# BoardA.net
KiCad netlist of a schematic drawn in Altium Designer
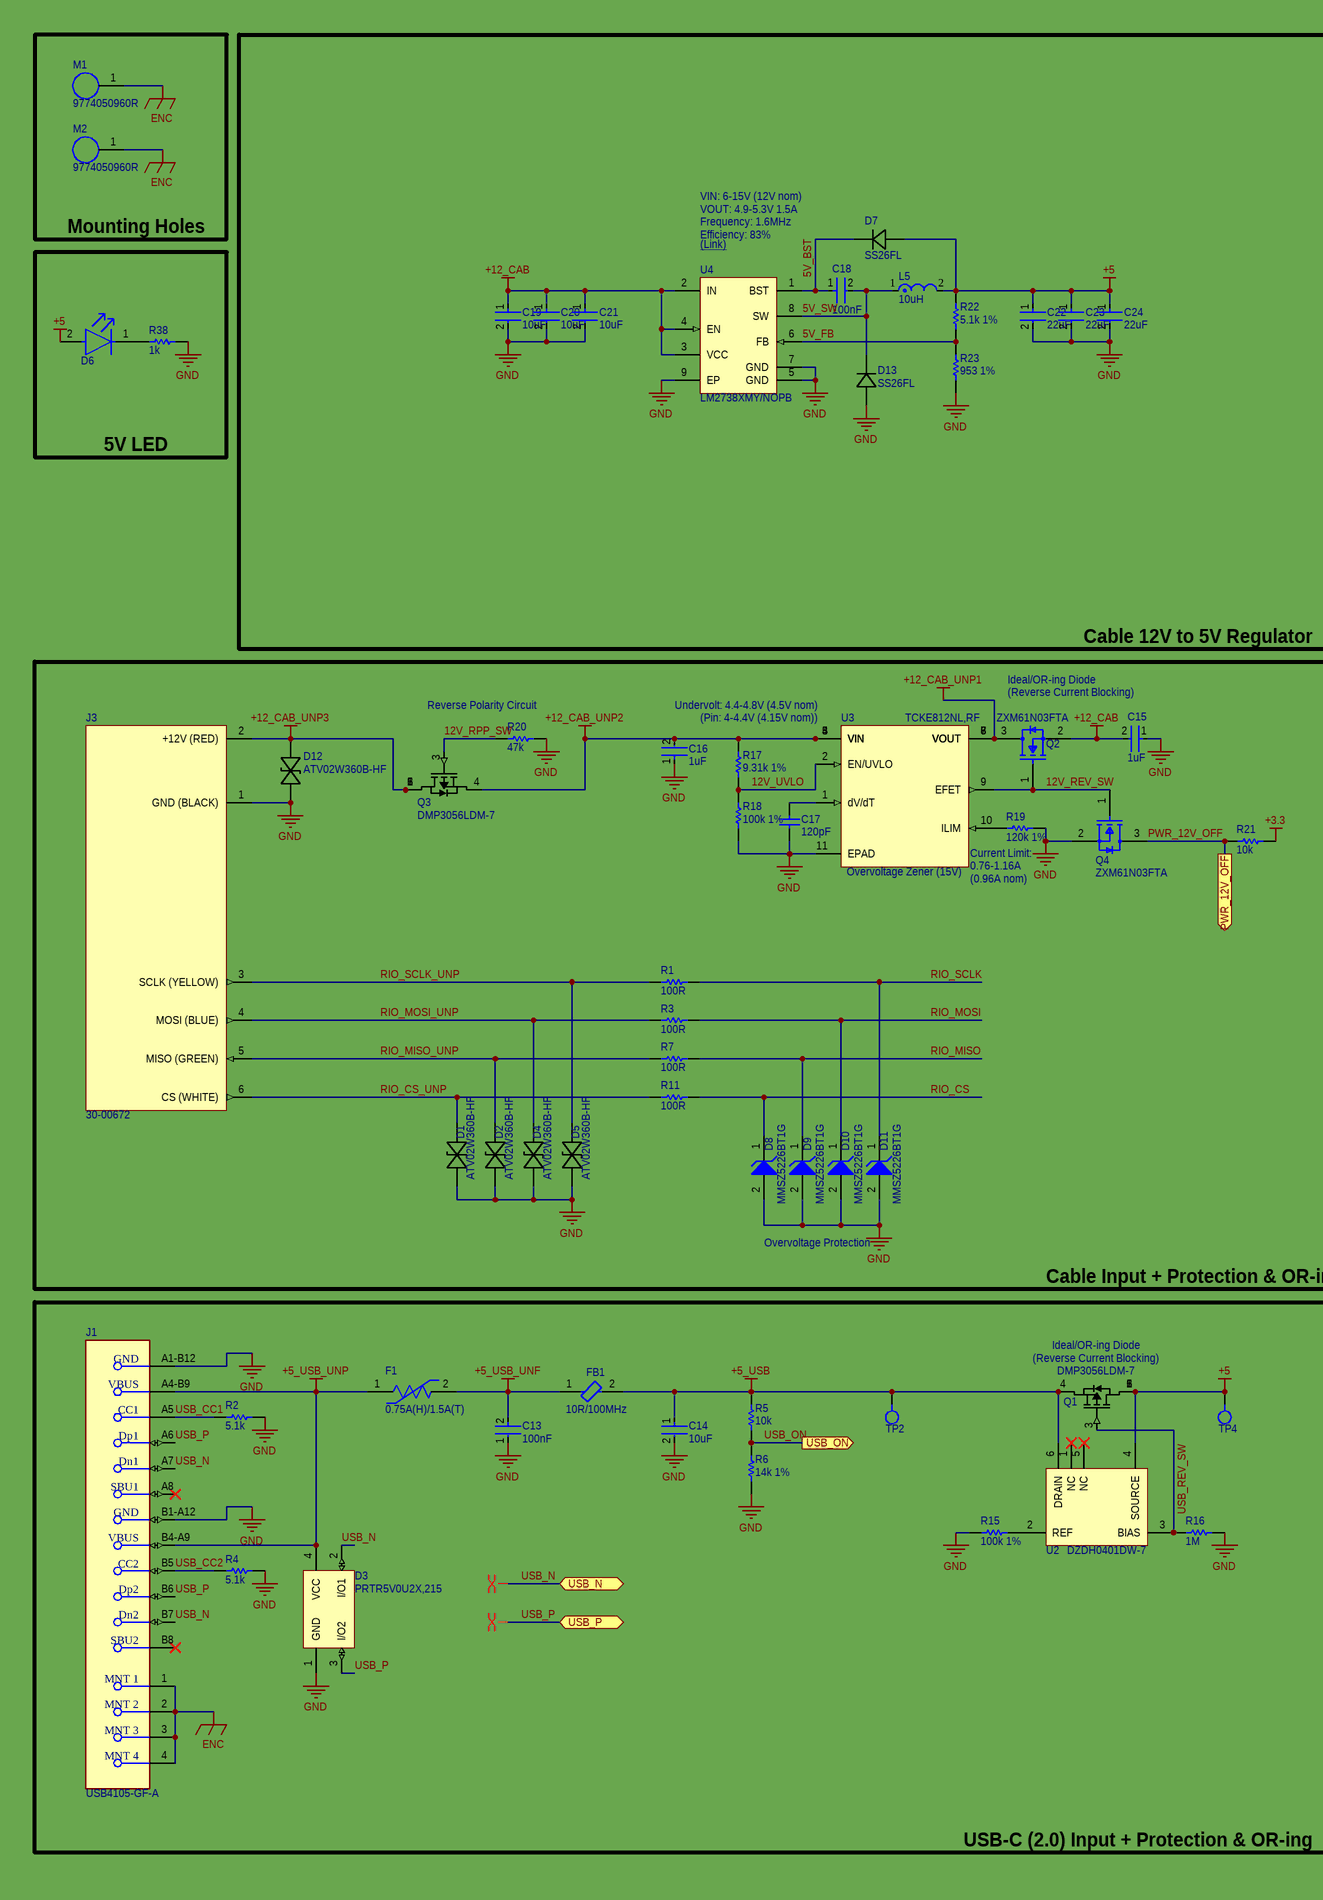
[diagram p0: BoardA.SchDoc, left]
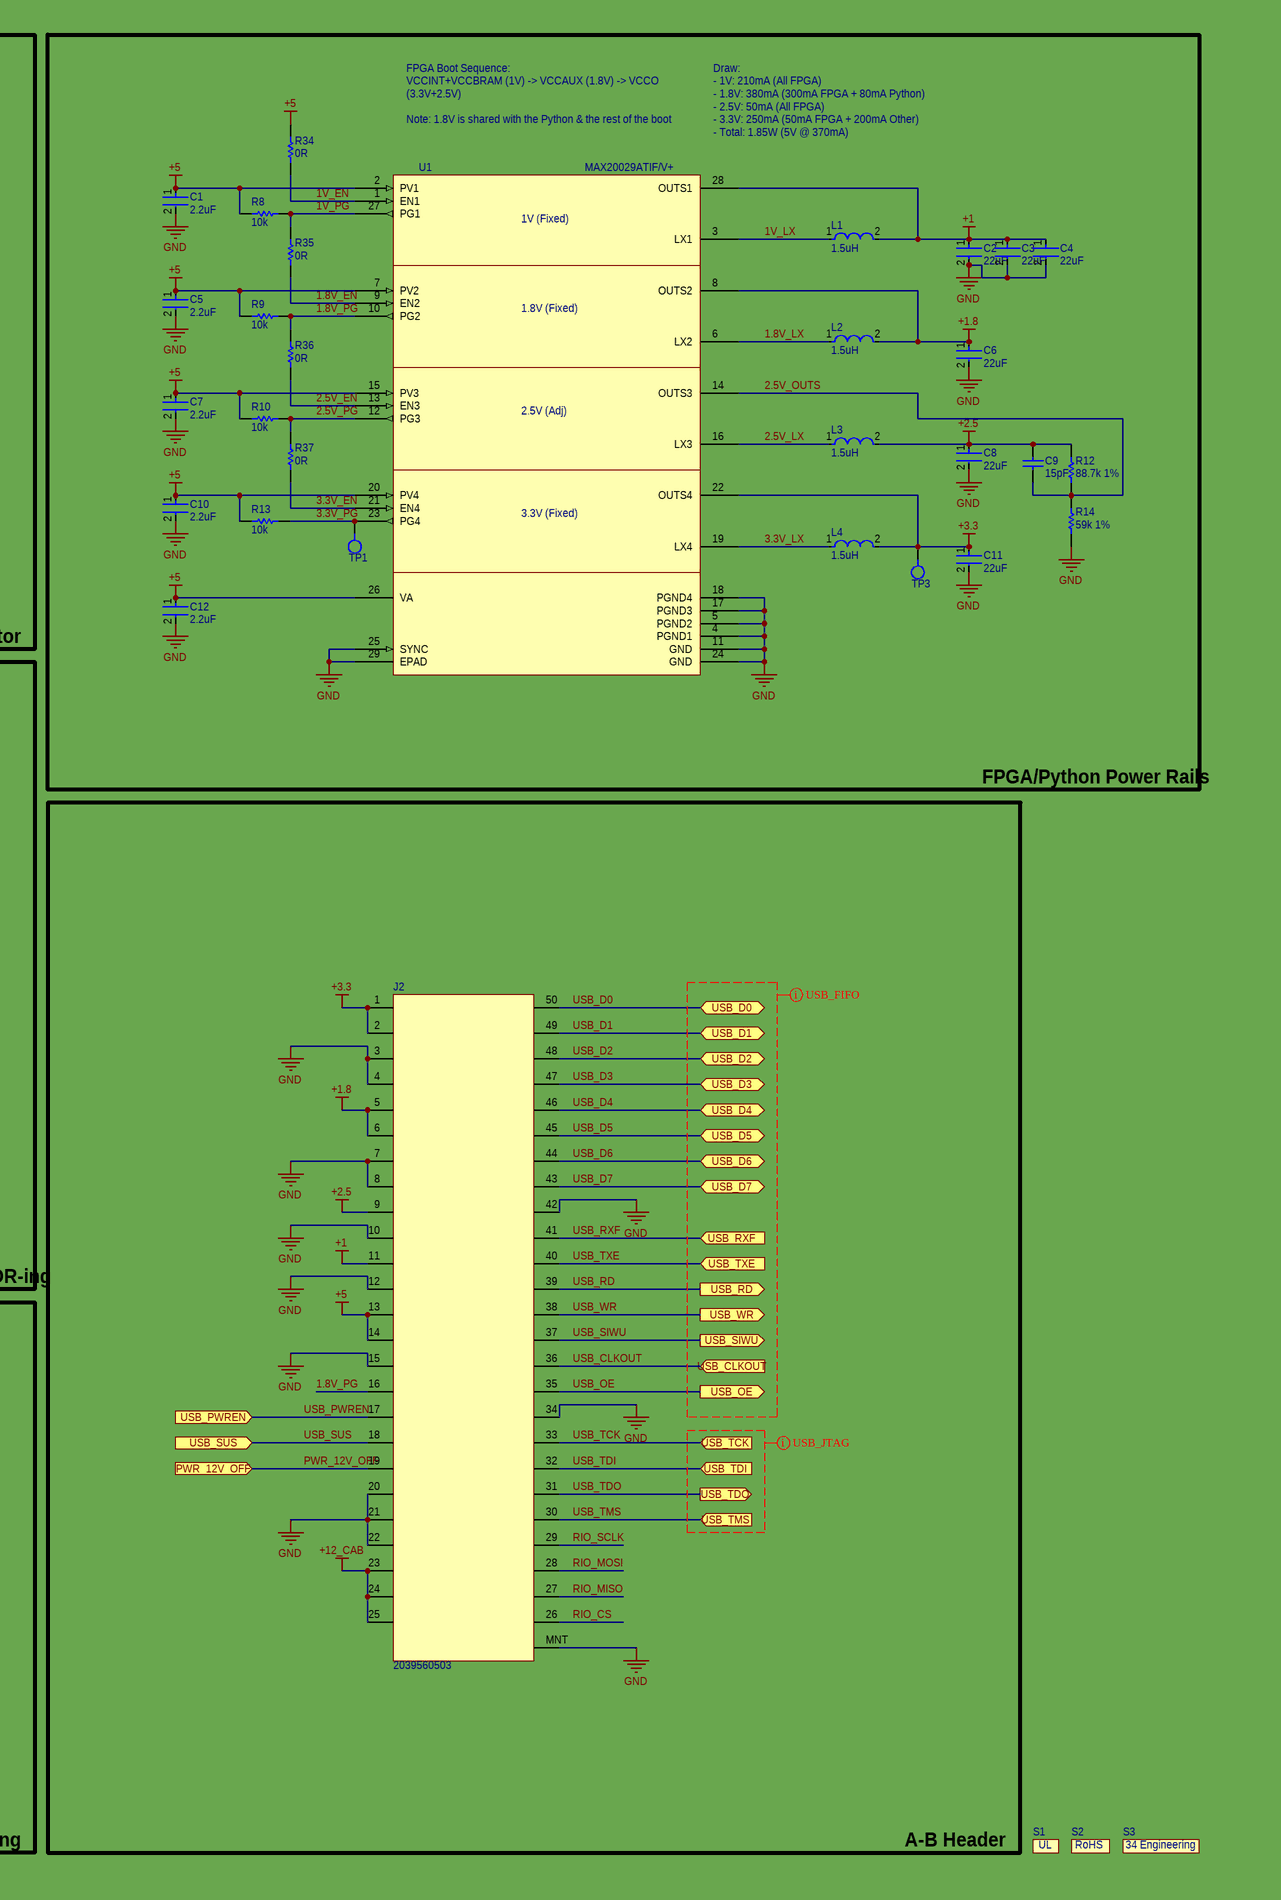
[diagram p1: BoardA.SchDoc, right]

(export (version "E")
  (design (tool "Eeschema 10.0.6"))
  (components
    (comp (ref "C1")
      (value "2.2uF")
      (footprint "FP-C1005-050-0_15-0_1-MFG")
      (description "CAP CER 2.2UF 10V X7S 0402")
      (fields (field (name "TOLERANCE") "10%"))
      (libsource (lib "Altium Content Vault") (part "b4654b650e69147ec39a6b967a45e02"))
    )
    (comp (ref "C2")
      (value "22uF")
      (footprint "FP-GRM21B-0_15-MFG")
      (description "Chip Multilayer Ceramic Capacitors for General Purpose, 0805, 22uF, X5R, 15%, 20%, 6.3V")
      (fields (field (name "VOLTAGE") "6.3V") (field (name "TOLERANCE") "20%"))
      (libsource (lib "Altium Content Vault") (part "b4654b650e69147ec39a6b967a45e02"))
    )
    (comp (ref "C3")
      (value "22uF")
      (footprint "FP-GRM21B-0_15-MFG")
      (description "Chip Multilayer Ceramic Capacitors for General Purpose, 0805, 22uF, X5R, 15%, 20%, 6.3V")
      (fields (field (name "VOLTAGE") "6.3V") (field (name "TOLERANCE") "20%"))
      (libsource (lib "Altium Content Vault") (part "b4654b650e69147ec39a6b967a45e02"))
    )
    (comp (ref "C4")
      (value "22uF")
      (footprint "FP-GRM21B-0_15-MFG")
      (description "Chip Multilayer Ceramic Capacitors for General Purpose, 0805, 22uF, X5R, 15%, 20%, 6.3V")
      (fields (field (name "VOLTAGE") "6.3V") (field (name "TOLERANCE") "20%"))
      (libsource (lib "Altium Content Vault") (part "b4654b650e69147ec39a6b967a45e02"))
    )
    (comp (ref "C5")
      (value "2.2uF")
      (footprint "FP-C1005-050-0_15-0_1-MFG")
      (description "CAP CER 2.2UF 10V X7S 0402")
      (fields (field (name "TOLERANCE") "10%"))
      (libsource (lib "Altium Content Vault") (part "b4654b650e69147ec39a6b967a45e02"))
    )
    (comp (ref "C6")
      (value "22uF")
      (footprint "FP-GRM21B-0_15-MFG")
      (description "Chip Multilayer Ceramic Capacitors for General Purpose, 0805, 22uF, X5R, 15%, 20%, 6.3V")
      (fields (field (name "VOLTAGE") "6.3V") (field (name "TOLERANCE") "20%"))
      (libsource (lib "Altium Content Vault") (part "b4654b650e69147ec39a6b967a45e02"))
    )
    (comp (ref "C7")
      (value "2.2uF")
      (footprint "FP-C1005-050-0_15-0_1-MFG")
      (description "CAP CER 2.2UF 10V X7S 0402")
      (fields (field (name "TOLERANCE") "10%"))
      (libsource (lib "Altium Content Vault") (part "b4654b650e69147ec39a6b967a45e02"))
    )
    (comp (ref "C8")
      (value "22uF")
      (footprint "FP-GRM21B-0_15-MFG")
      (description "Chip Multilayer Ceramic Capacitors for General Purpose, 0805, 22uF, X5R, 15%, 20%, 6.3V")
      (fields (field (name "VOLTAGE") "6.3V") (field (name "TOLERANCE") "20%"))
      (libsource (lib "Altium Content Vault") (part "b4654b650e69147ec39a6b967a45e02"))
    )
    (comp (ref "C9")
      (value "15pF")
      (footprint "CAPC1005X55X25NL05T10")
      (fields (field (name "PART NUMBER") "GRM1555C1H150JZ01D") (field (name "MANUFACTURER") "Murata"))
      (libsource (lib "Altium Content Vault") (part "CAP"))
    )
    (comp (ref "C10")
      (value "2.2uF")
      (footprint "FP-C1005-050-0_15-0_1-MFG")
      (description "CAP CER 2.2UF 10V X7S 0402")
      (fields (field (name "TOLERANCE") "10%"))
      (libsource (lib "Altium Content Vault") (part "b4654b650e69147ec39a6b967a45e02"))
    )
    (comp (ref "C11")
      (value "22uF")
      (footprint "FP-GRM21B-0_15-MFG")
      (description "Chip Multilayer Ceramic Capacitors for General Purpose, 0805, 22uF, X5R, 15%, 20%, 6.3V")
      (fields (field (name "VOLTAGE") "6.3V") (field (name "TOLERANCE") "20%"))
      (libsource (lib "Altium Content Vault") (part "b4654b650e69147ec39a6b967a45e02"))
    )
    (comp (ref "C12")
      (value "2.2uF")
      (footprint "FP-C1005-050-0_15-0_1-MFG")
      (description "CAP CER 2.2UF 10V X7S 0402")
      (fields (field (name "TOLERANCE") "10%"))
      (libsource (lib "Altium Content Vault") (part "b4654b650e69147ec39a6b967a45e02"))
    )
    (comp (ref "C13")
      (value "100nF")
      (footprint "FP-GRM15-IPC_C")
      (description "CAP CER 0.1UF 16V X7R 0402")
      (fields (field (name "MANUFACTURER PART NUMBER") "GRM155R71C104KA88D") (field (name "TOLERANCE") "10%"))
      (libsource (lib "Altium Content Vault") (part "236180d848d6139a670b325ea6854c9"))
    )
    (comp (ref "C14")
      (value "10uF")
      (footprint "FP-CL05A106MP5NUNC-IPC_B")
      (description "CAP CER 10UF 10V X5R 0402")
      (fields
        (field (name "OCTOPART") "https://octopart.com/cl05a106mp5nunc-samsung-22457395")
        (field (name "TOLERANCE") "20%")
      )
      (libsource (lib "Altium Content Vault") (part "b4654b650e69147ec39a6b967a45e02"))
    )
    (comp (ref "C15")
      (value "1uF")
      (footprint "FP-0603-L_1_6_0_1-W_0_8_0-IPC_B")
      (description "None")
      (fields (field (name "TOLERANCE") "10%"))
      (libsource (lib "Altium Content Vault") (part "02cd4be3c70576c341d710602a673aa"))
    )
    (comp (ref "C16")
      (value "1uF")
      (footprint "FP-0603-L_1_6_0_1-W_0_8_0-IPC_B")
      (description "None")
      (fields (field (name "TOLERANCE") "10%"))
      (libsource (lib "Altium Content Vault") (part "02cd4be3c70576c341d710602a673aa"))
    )
    (comp (ref "C17")
      (value "120pF")
      (footprint "CAPC1005X55X25ML05T10")
      (fields (field (name "MANUFACTURER") "Murata") (field (name "PART NUMBER") "GRM1555C1H121JA01D"))
      (libsource (lib "Altium Content Vault") (part "CAP"))
    )
    (comp (ref "C18")
      (value "100nF")
      (footprint "FP-CGA3E-0_3-0_1-IPC_C")
      (description "Cap Ceramic 100nF 50V X7R 10% Pad SMD 0603 +125°C Automotive T/R")
      (fields (field (name "TOLERANCE") "10%") (field (name "VOLTAGE") "50V"))
      (libsource (lib "Altium Content Vault") (part "b4654b650e69147ec39a6b967a45e02"))
    )
    (comp (ref "C19")
      (value "10uF")
      (footprint "FP-GRM188-0_2-MFG")
      (description "Chip Multilayer Ceramic Capacitors for General Purpose, 0603, 10uF, X5R, 15%, 20%, 25V")
      (fields (field (name "TOLERANCE") "20%") (field (name "VOLTAGE") "25V"))
      (libsource (lib "Altium Content Vault") (part "11868f565c42a9108669ba33697ecf6"))
    )
    (comp (ref "C20")
      (value "10uF")
      (footprint "FP-GRM188-0_2-MFG")
      (description "Chip Multilayer Ceramic Capacitors for General Purpose, 0603, 10uF, X5R, 15%, 20%, 25V")
      (fields (field (name "TOLERANCE") "20%") (field (name "VOLTAGE") "25V"))
      (libsource (lib "Altium Content Vault") (part "11868f565c42a9108669ba33697ecf6"))
    )
    (comp (ref "C21")
      (value "10uF")
      (footprint "FP-GRM188-0_2-MFG")
      (description "Chip Multilayer Ceramic Capacitors for General Purpose, 0603, 10uF, X5R, 15%, 20%, 25V")
      (fields (field (name "TOLERANCE") "20%") (field (name "VOLTAGE") "25V"))
      (libsource (lib "Altium Content Vault") (part "11868f565c42a9108669ba33697ecf6"))
    )
    (comp (ref "C22")
      (value "22uF")
      (footprint "FP-GRM21B-0_15-MFG")
      (description "Chip Multilayer Ceramic Capacitors for General Purpose, 0805, 22uF, X5R, 15%, 20%, 6.3V")
      (fields (field (name "VOLTAGE") "6.3V") (field (name "TOLERANCE") "20%"))
      (libsource (lib "Altium Content Vault") (part "b4654b650e69147ec39a6b967a45e02"))
    )
    (comp (ref "C23")
      (value "22uF")
      (footprint "FP-GRM21B-0_15-MFG")
      (description "Chip Multilayer Ceramic Capacitors for General Purpose, 0805, 22uF, X5R, 15%, 20%, 6.3V")
      (fields (field (name "VOLTAGE") "6.3V") (field (name "TOLERANCE") "20%"))
      (libsource (lib "Altium Content Vault") (part "b4654b650e69147ec39a6b967a45e02"))
    )
    (comp (ref "C24")
      (value "22uF")
      (footprint "FP-GRM21B-0_15-MFG")
      (description "Chip Multilayer Ceramic Capacitors for General Purpose, 0805, 22uF, X5R, 15%, 20%, 6.3V")
      (fields (field (name "VOLTAGE") "6.3V") (field (name "TOLERANCE") "20%"))
      (libsource (lib "Altium Content Vault") (part "b4654b650e69147ec39a6b967a45e02"))
    )
    (comp (ref "D1")
      (value "ATV02W360B-HF")
      (footprint "ATV02W")
      (description "No Description Available")
      (fields (field (name "COPYRIGHT") "Copyright (C) 2022 Ultra Librarian. All rights reserved."))
      (libsource (lib "Virtex") (part "ATV02W360B-HF"))
    )
    (comp (ref "D2")
      (value "ATV02W360B-HF")
      (footprint "ATV02W")
      (description "No Description Available")
      (fields (field (name "COPYRIGHT") "Copyright (C) 2022 Ultra Librarian. All rights reserved."))
      (libsource (lib "Virtex") (part "ATV02W360B-HF"))
    )
    (comp (ref "D3")
      (value "PRTR5V0U2X,215")
      (footprint "NXP-SOT143B-4_V")
      (fields (field (name "MANUFACTURER") "NXP Semiconductors"))
      (libsource (lib "Altium Content Vault") (part "NXP-PRTR5V0U2X,215-4"))
    )
    (comp (ref "D4")
      (value "ATV02W360B-HF")
      (footprint "ATV02W")
      (description "No Description Available")
      (fields (field (name "COPYRIGHT") "Copyright (C) 2022 Ultra Librarian. All rights reserved."))
      (libsource (lib "Virtex") (part "ATV02W360B-HF"))
    )
    (comp (ref "D5")
      (value "ATV02W360B-HF")
      (footprint "ATV02W")
      (description "No Description Available")
      (fields (field (name "COPYRIGHT") "Copyright (C) 2022 Ultra Librarian. All rights reserved."))
      (libsource (lib "Virtex") (part "ATV02W360B-HF"))
    )
    (comp (ref "D6")
      (value "SML-D12U1WT86")
      (footprint "FP-SML-D12-MFG")
      (description "LED RED DIFFUSED 1608 SMD")
      (fields
        (field (name "MANUFACTURER") "Rohm")
        (field (name "OCTOPART") "https://octopart.com/sml-d12u1wt86-rohm-70850259")
      )
      (libsource (lib "Altium Content Vault") (part "8706943c75ba83719d021d2fdc84c58"))
    )
    (comp (ref "D7")
      (value "SS26FL")
      (footprint "SS26FL")
      (description "Diode Schottky Barrier Rectifier 60V 2A 2-Pin SOD-123F T/R")
      (fields (field (name "MANUFACTURER") "ON Semiconductor / Fairchild"))
      (libsource (lib "Virtex") (part "SS26FL"))
    )
    (comp (ref "D8")
      (value "MMSZ5226BT1G")
      (footprint "ONSC-SOD-123-2-425-04_V")
      (description "Zener Voltage Regulator, 500 mW, 2-Pin SOD-123, Pb-Free, Tape and Reel")
      (fields (field (name "MANUFACTURER") "On Semiconductor"))
      (libsource (lib "Altium Content Vault") (part "ONSC-K1A2-2"))
    )
    (comp (ref "D9")
      (value "MMSZ5226BT1G")
      (footprint "ONSC-SOD-123-2-425-04_V")
      (description "Zener Voltage Regulator, 500 mW, 2-Pin SOD-123, Pb-Free, Tape and Reel")
      (fields (field (name "MANUFACTURER") "On Semiconductor"))
      (libsource (lib "Altium Content Vault") (part "ONSC-K1A2-2"))
    )
    (comp (ref "D10")
      (value "MMSZ5226BT1G")
      (footprint "ONSC-SOD-123-2-425-04_V")
      (description "Zener Voltage Regulator, 500 mW, 2-Pin SOD-123, Pb-Free, Tape and Reel")
      (fields (field (name "MANUFACTURER") "On Semiconductor"))
      (libsource (lib "Altium Content Vault") (part "ONSC-K1A2-2"))
    )
    (comp (ref "D11")
      (value "MMSZ5226BT1G")
      (footprint "ONSC-SOD-123-2-425-04_V")
      (description "Zener Voltage Regulator, 500 mW, 2-Pin SOD-123, Pb-Free, Tape and Reel")
      (fields (field (name "MANUFACTURER") "On Semiconductor"))
      (libsource (lib "Altium Content Vault") (part "ONSC-K1A2-2"))
    )
    (comp (ref "D12")
      (value "ATV02W360B-HF")
      (footprint "ATV02W")
      (description "No Description Available")
      (fields (field (name "COPYRIGHT") "Copyright (C) 2022 Ultra Librarian. All rights reserved."))
      (libsource (lib "Virtex") (part "ATV02W360B-HF"))
    )
    (comp (ref "D13")
      (value "SS26FL")
      (footprint "SS26FL")
      (description "Diode Schottky Barrier Rectifier 60V 2A 2-Pin SOD-123F T/R")
      (fields (field (name "MANUFACTURER") "ON Semiconductor / Fairchild"))
      (libsource (lib "Virtex") (part "SS26FL"))
    )
    (comp (ref "F1")
      (value "0.75A(H)/1.5A(T)")
      (footprint "FP-0ZCK0075FF2E-MFG")
      (description "PTC RESET FUSE 6V 750MA 0805")
      (libsource (lib "Altium Content Vault") (part "fdf083d5f6389a9a1c4e51137f46658"))
    )
    (comp (ref "FB1")
      (value "10R/100MHz")
      (footprint "FP-BLM15-0_05-IPC_A")
      (description "Chip Ferrite Bead, 0402, 10Ω @ 100MHz, 0.025Ω, 25%, 1A")
      (fields (field (name "TOLERANCE") "25%"))
      (libsource (lib "Altium Content Vault") (part "5f30dd21d616792df468990f7003faa"))
    )
    (comp (ref "J1")
      (value "USB4105-GF-A")
      (footprint "FP-USB4105-GF-A-MFG")
      (description "CONN RCPT USB2.0 TYPEC 5A")
      (fields
        (field (name "MANUFACTURER") "GCT")
        (field (name "OCTOPART") "https://octopart.com/usb4105-gf-a-gct-106627878")
      )
      (libsource (lib "Altium Content Vault") (part "e7c17a616881a82b79941196b4bec10"))
    )
    (comp (ref "J2")
      (value "2039560503")
      (footprint "2039560503")
      (fields (field (name "MANUFACTURER") "Molex") (field (name "MANUFACTURER PART NUMBER") "203956-0503"))
      (libsource (lib "Virtex") (part "2039560503"))
    )
    (comp (ref "J3")
      (value "30-00672")
      (footprint "30-00672")
      (description "Multi-Conductor Cable Braid Thermoplastic Elastomer 6Conductors 28AWG 4.9mm 300V Black")
      (fields (field (name "MANUFACTURER") "Tensility") (field (name "VOLTAGE") "300V"))
      (libsource (lib "Virtex") (part "30-00672"))
    )
    (comp (ref "L1")
      (value "1.5uH")
      (footprint "FP-DFE252012C-IPC_C")
      (description "Shielded Wirewound Inductor 1.5uH 20% 2600mA 0.06Ω 1008 (2520)")
      (fields (field (name "TOLERANCE") "20%"))
      (libsource (lib "Altium Content Vault") (part "725321dda6339637d4d059423bc1c3c"))
    )
    (comp (ref "L2")
      (value "1.5uH")
      (footprint "FP-DFE252012C-IPC_C")
      (description "Shielded Wirewound Inductor 1.5uH 20% 2600mA 0.06Ω 1008 (2520)")
      (fields (field (name "TOLERANCE") "20%"))
      (libsource (lib "Altium Content Vault") (part "725321dda6339637d4d059423bc1c3c"))
    )
    (comp (ref "L3")
      (value "1.5uH")
      (footprint "FP-DFE252012C-IPC_C")
      (description "Shielded Wirewound Inductor 1.5uH 20% 2600mA 0.06Ω 1008 (2520)")
      (fields (field (name "TOLERANCE") "20%"))
      (libsource (lib "Altium Content Vault") (part "725321dda6339637d4d059423bc1c3c"))
    )
    (comp (ref "L4")
      (value "1.5uH")
      (footprint "FP-DFE252012C-IPC_C")
      (description "Shielded Wirewound Inductor 1.5uH 20% 2600mA 0.06Ω 1008 (2520)")
      (fields (field (name "TOLERANCE") "20%"))
      (libsource (lib "Altium Content Vault") (part "725321dda6339637d4d059423bc1c3c"))
    )
    (comp (ref "L5")
      (value "10uH")
      (footprint "FP-VLS6045EX-100M-MFG")
      (description "FIXED IND 10UH 3.4A 61 MOHM SMD")
      (fields (field (name "TOLERANCE") "20%"))
      (libsource (lib "Altium Content Vault") (part "4cc4b267dca4c8e51f7102f422741d8"))
    )
    (comp (ref "M1")
      (value "9774050960R")
      (footprint "9774050960R")
      (description "Spacer Material: Steel Mounting: SMT Series: WA-SMST For ø: 3.3 mm")
      (fields
        (field (name "MANUFACTURER") "Wurth Electronics")
        (field (name "MANUFACTURER PART NUMBER") "9774070960R")
      )
      (libsource (lib "Virtex") (part "9774050960R"))
    )
    (comp (ref "M2")
      (value "9774050960R")
      (footprint "9774050960R")
      (description "Spacer Material: Steel Mounting: SMT Series: WA-SMST For ø: 3.3 mm")
      (fields
        (field (name "MANUFACTURER") "Wurth Electronics")
        (field (name "MANUFACTURER PART NUMBER") "9774070960R")
      )
      (libsource (lib "Virtex") (part "9774050960R"))
    )
    (comp (ref "Q1")
      (value "DMP3056LDM-7")
      (footprint "SOT95P285X130-6N")
      (description "Trans Mosfet P-ch 30V 4.3A 6-PIN SOT-26 T/r / Mosfet P-ch 30V 4.3A SOT-26")
      (fields
        (field (name "MANUFACTURER_PART_NUMBER") "DMG4407SSS-13")
        (field (name "MANUFACTURER") "Diodes")
        (field (name "COPYRIGHT") "Copyright (C) 2022 Ultra Librarian. All rights reserved.")
      )
      (libsource (lib "Virtex") (part "DMP3056LDM-7"))
    )
    (comp (ref "Q2")
      (value "ZXM61N03FTA")
      (footprint "FP-SOT23-MFG")
      (description "MOSFET N-CH 30V 1.4A SOT23-3")
      (fields
        (field (name "MANUFACTURER") "Diodes Inc.")
        (field (name "OCTOPART") "https://octopart.com/zxm61n03fta-diodes+inc.-660007")
      )
      (libsource (lib "Altium Content Vault") (part "f26a002bc83f1905f63347c14e5b235"))
    )
    (comp (ref "Q3")
      (value "DMP3056LDM-7")
      (footprint "SOT95P285X130-6N")
      (description "Trans Mosfet P-ch 30V 4.3A 6-PIN SOT-26 T/r / Mosfet P-ch 30V 4.3A SOT-26")
      (fields
        (field (name "MANUFACTURER_PART_NUMBER") "DMG4407SSS-13")
        (field (name "MANUFACTURER") "Diodes")
        (field (name "COPYRIGHT") "Copyright (C) 2022 Ultra Librarian. All rights reserved.")
      )
      (libsource (lib "Virtex") (part "DMP3056LDM-7"))
    )
    (comp (ref "Q4")
      (value "ZXM61N03FTA")
      (footprint "FP-SOT23-MFG")
      (description "MOSFET N-CH 30V 1.4A SOT23-3")
      (fields
        (field (name "MANUFACTURER") "Diodes Inc.")
        (field (name "OCTOPART") "https://octopart.com/zxm61n03fta-diodes+inc.-660007")
      )
      (libsource (lib "Altium Content Vault") (part "f26a002bc83f1905f63347c14e5b235"))
    )
    (comp (ref "R1")
      (value "100R")
      (footprint "RESC2013X60X35ML10T20")
      (description "Chip Resistor, 100 Ohm, +/-1%, 0.125 W, -55 to 155 degC, 0805 (2012 Metric), RoHS, Tape and Reel")
      (fields (field (name "TOLERANCE") "1%") (field (name "MANUFACTURER") "Yageo"))
      (libsource (lib "Altium Content Vault") (part "RES-2"))
    )
    (comp (ref "R2")
      (value "5.1k")
      (footprint "RESC1005X40X25LL10T10")
      (fields
        (field (name "MANUFACTURER") "TE Connectivity / AMP")
        (field (name "PART NUMBER") "CRG0402F5K1")
      )
      (libsource (lib "Altium Content Vault") (part "RES"))
    )
    (comp (ref "R3")
      (value "100R")
      (footprint "RESC2013X60X35ML10T20")
      (description "Chip Resistor, 100 Ohm, +/-1%, 0.125 W, -55 to 155 degC, 0805 (2012 Metric), RoHS, Tape and Reel")
      (fields (field (name "TOLERANCE") "1%") (field (name "MANUFACTURER") "Yageo"))
      (libsource (lib "Altium Content Vault") (part "RES-2"))
    )
    (comp (ref "R4")
      (value "5.1k")
      (footprint "RESC1005X40X25LL10T10")
      (fields
        (field (name "MANUFACTURER") "TE Connectivity / AMP")
        (field (name "PART NUMBER") "CRG0402F5K1")
      )
      (libsource (lib "Altium Content Vault") (part "RES"))
    )
    (comp (ref "R5")
      (value "10k")
      (footprint "RESC1005X40X25LL05T05")
      (description "Chip Resistor, 10 KOhm, +/- 1%, 0.1 W, -55 to 155 degC, 0402 (1005 Metric), RoHS, Tape and Reel")
      (fields (field (name "TOLERANCE") "1%") (field (name "MANUFACTURER") "Panasonic"))
      (libsource (lib "Altium Content Vault") (part "RES-2"))
    )
    (comp (ref "R6")
      (value "14k 1%")
      (footprint "RESC1005X40X25ML05T05")
      (fields (field (name "MANUFACTURER") "Panasonic") (field (name "PART NUMBER") "ERJ-2RKF1402X"))
      (libsource (lib "Altium Content Vault") (part "RES"))
    )
    (comp (ref "R7")
      (value "100R")
      (footprint "RESC2013X60X35ML10T20")
      (description "Chip Resistor, 100 Ohm, +/-1%, 0.125 W, -55 to 155 degC, 0805 (2012 Metric), RoHS, Tape and Reel")
      (fields (field (name "TOLERANCE") "1%") (field (name "MANUFACTURER") "Yageo"))
      (libsource (lib "Altium Content Vault") (part "RES-2"))
    )
    (comp (ref "R8")
      (value "10k")
      (footprint "RESC1005X40X25LL05T05")
      (description "Chip Resistor, 10 KOhm, +/- 1%, 0.1 W, -55 to 155 degC, 0402 (1005 Metric), RoHS, Tape and Reel")
      (fields (field (name "TOLERANCE") "1%") (field (name "MANUFACTURER") "Panasonic"))
      (libsource (lib "Altium Content Vault") (part "RES-2"))
    )
    (comp (ref "R9")
      (value "10k")
      (footprint "RESC1005X40X25LL05T05")
      (description "Chip Resistor, 10 KOhm, +/- 1%, 0.1 W, -55 to 155 degC, 0402 (1005 Metric), RoHS, Tape and Reel")
      (fields (field (name "TOLERANCE") "1%") (field (name "MANUFACTURER") "Panasonic"))
      (libsource (lib "Altium Content Vault") (part "RES-2"))
    )
    (comp (ref "R10")
      (value "10k")
      (footprint "RESC1005X40X25LL05T05")
      (description "Chip Resistor, 10 KOhm, +/- 1%, 0.1 W, -55 to 155 degC, 0402 (1005 Metric), RoHS, Tape and Reel")
      (fields (field (name "TOLERANCE") "1%") (field (name "MANUFACTURER") "Panasonic"))
      (libsource (lib "Altium Content Vault") (part "RES-2"))
    )
    (comp (ref "R11")
      (value "100R")
      (footprint "RESC2013X60X35ML10T20")
      (description "Chip Resistor, 100 Ohm, +/-1%, 0.125 W, -55 to 155 degC, 0805 (2012 Metric), RoHS, Tape and Reel")
      (fields (field (name "TOLERANCE") "1%") (field (name "MANUFACTURER") "Yageo"))
      (libsource (lib "Altium Content Vault") (part "RES-2"))
    )
    (comp (ref "R12")
      (value "88.7k 1%")
      (footprint "RESC1005X40X25NL05T05")
      (fields (field (name "MANUFACTURER") "Vishay Dale") (field (name "PART NUMBER") "CRCW040288K7FKED"))
      (libsource (lib "Altium Content Vault") (part "RES"))
    )
    (comp (ref "R13")
      (value "10k")
      (footprint "RESC1005X40X25LL05T05")
      (description "Chip Resistor, 10 KOhm, +/- 1%, 0.1 W, -55 to 155 degC, 0402 (1005 Metric), RoHS, Tape and Reel")
      (fields (field (name "TOLERANCE") "1%") (field (name "MANUFACTURER") "Panasonic"))
      (libsource (lib "Altium Content Vault") (part "RES-2"))
    )
    (comp (ref "R14")
      (value "59k 1%")
      (footprint "RESC1005X40X25LL05T05")
      (fields (field (name "PART NUMBER") "CRCW040259K0FKED") (field (name "MANUFACTURER") "Vishay Dale"))
      (libsource (lib "Altium Content Vault") (part "RES"))
    )
    (comp (ref "R15")
      (value "100k 1%")
      (footprint "RESC1005X40X25NL05T10")
      (fields (field (name "PART NUMBER") "RC0402FR-07100KL") (field (name "MANUFACTURER") "Yageo / Phycomp"))
      (libsource (lib "Altium Content Vault") (part "RES"))
    )
    (comp (ref "R16")
      (value "1M")
      (footprint "RESC1005X40X25LL05T05")
      (description "Chip Resistor, 1 MOhm, +/- 1%, 100 mW, -55 to 155 degC, 0402 (1005 Metric), RoHS, Tape and Reel")
      (fields (field (name "PARTNUMBER") "ERJ-2RKF1004X") (field (name "TOLERANCE") "1%"))
      (libsource (lib "Altium Content Vault") (part "RES-2"))
    )
    (comp (ref "R17")
      (value "9.31k 1%")
      (footprint "RESC1005X40X25NL05T05")
      (fields (field (name "PART NUMBER") "ERJ-2RKF9311X") (field (name "MANUFACTURER") "Panasonic"))
      (libsource (lib "Altium Content Vault") (part "RES"))
    )
    (comp (ref "R18")
      (value "100k 1%")
      (footprint "RESC1005X40X25NL05T10")
      (fields (field (name "PART NUMBER") "RC0402FR-07100KL") (field (name "MANUFACTURER") "Yageo / Phycomp"))
      (libsource (lib "Altium Content Vault") (part "RES"))
    )
    (comp (ref "R19")
      (value "120k 1%")
      (footprint "RESC1005X40X25NL05T05")
      (fields (field (name "PART NUMBER") "ERJ2RKF1203X") (field (name "MANUFACTURER") "Panasonic"))
      (libsource (lib "Altium Content Vault") (part "RES"))
    )
    (comp (ref "R20")
      (value "47k")
      (footprint "RESC1608X55X30NL15T15")
      (description "Chip Resistor, 47 KOhm, +/- 1%, 0.1 W, -55 to 155 degC, 0603 (1608 Metric), RoHS, Tape and Reel")
      (libsource (lib "Altium Content Vault") (part "RES-2"))
    )
    (comp (ref "R21")
      (value "10k")
      (footprint "RESC1005X40X25LL05T05")
      (description "Chip Resistor, 10 KOhm, +/- 1%, 0.1 W, -55 to 155 degC, 0402 (1005 Metric), RoHS, Tape and Reel")
      (fields (field (name "TOLERANCE") "1%") (field (name "MANUFACTURER") "Panasonic"))
      (libsource (lib "Altium Content Vault") (part "RES-2"))
    )
    (comp (ref "R22")
      (value "5.1k 1%")
      (footprint "RESC1608X55X30NL15T15")
      (fields (field (name "PART NUMBER") "ERJ-3EKF5101V") (field (name "MANUFACTURER") "Panasonic"))
      (libsource (lib "Altium Content Vault") (part "RES"))
    )
    (comp (ref "R23")
      (value "953 1%")
      (footprint "RESC1608X55X30NL15T15")
      (fields (field (name "PART NUMBER") "ERJ-3EKF9530V") (field (name "MANUFACTURER") "Panasonic"))
      (libsource (lib "Altium Content Vault") (part "RES"))
    )
    (comp (ref "R34")
      (value "0R")
      (footprint "RESC1005X40X25NL05T10")
      (fields (field (name "MANUFACTURER") "Yageo / Phycomp") (field (name "PART NUMBER") "RC0402JR-070RL"))
      (libsource (lib "Altium Content Vault") (part "RES"))
    )
    (comp (ref "R35")
      (value "0R")
      (footprint "RESC1005X40X25NL05T10")
      (fields (field (name "MANUFACTURER") "Yageo / Phycomp") (field (name "PART NUMBER") "RC0402JR-070RL"))
      (libsource (lib "Altium Content Vault") (part "RES"))
    )
    (comp (ref "R36")
      (value "0R")
      (footprint "RESC1005X40X25NL05T10")
      (fields (field (name "MANUFACTURER") "Yageo / Phycomp") (field (name "PART NUMBER") "RC0402JR-070RL"))
      (libsource (lib "Altium Content Vault") (part "RES"))
    )
    (comp (ref "R37")
      (value "0R")
      (footprint "RESC1005X40X25NL05T10")
      (fields (field (name "MANUFACTURER") "Yageo / Phycomp") (field (name "PART NUMBER") "RC0402JR-070RL"))
      (libsource (lib "Altium Content Vault") (part "RES"))
    )
    (comp (ref "R38")
      (value "1k")
      (footprint "RESC1005X40X25NL05T05")
      (description "Chip Resistor, 1 KOhm, +/- 1%, 100 mW, -55 to 155 degC, 0402 (1005 Metric), RoHS, Tape and Reel")
      (fields (field (name "PARTNUMBER") "ERJ-2RKF1001X") (field (name "MANUFACTURER") "Basic Passives"))
      (libsource (lib "Altium Content Vault") (part "RES-2"))
    )
    (comp (ref "S1") (value "~") (footprint "UL") (libsource (lib "Virtex") (part "UL")))
    (comp (ref "S2") (value "~") (footprint "RoHS") (libsource (lib "Virtex") (part "RoHS")))
    (comp (ref "S3")
      (value "~")
      (footprint "34EngineeringLogo")
      (description "34 Engineering Silkscreen Logo")
      (libsource (lib "Virtex") (part "34EngineeringLogo"))
    )
    (comp (ref "TP1")
      (value "~")
      (footprint "TestPoint1mm")
      (description "Test Point 1mm Diameter")
      (libsource (lib "Virtex") (part "TestPoint1mm"))
    )
    (comp (ref "TP2")
      (value "~")
      (footprint "TestPoint1mm")
      (description "Test Point 1mm Diameter")
      (libsource (lib "Virtex") (part "TestPoint1mm"))
    )
    (comp (ref "TP3")
      (value "~")
      (footprint "TestPoint1mm")
      (description "Test Point 1mm Diameter")
      (libsource (lib "Virtex") (part "TestPoint1mm"))
    )
    (comp (ref "TP4")
      (value "~")
      (footprint "TestPoint1mm")
      (description "Test Point 1mm Diameter")
      (libsource (lib "Virtex") (part "TestPoint1mm"))
    )
    (comp (ref "U1")
      (value "MAX20029ATIF/V+")
      (footprint "MAX20029ATIF/V+")
      (description "DC to DC Converter Quad Step-Down 3V to 5.5V Automotive 28-Pin TQFN Tube")
      (fields
        (field (name "MANUFACTURER") "Maxim")
        (field (name "COPYRIGHT") "Copyright (C) 2022 Ultra Librarian. All rights reserved.")
      )
      (libsource (lib "Virtex") (part "MAX20029ATIF/V+"))
    )
    (comp (ref "U2")
      (value "DZDH0401DW-7")
      (footprint "DZDH0401DW-7")
      (description "Ideal Diode Controller 40V 300mA 300mW 6-Pin SOT-363 T/R")
      (fields
        (field (name "MANUFACTURER") "Diodes")
        (field (name "COPYRIGHT") "Copyright (C) 2022 Ultra Librarian. All rights reserved.")
      )
      (libsource (lib "Virtex") (part "DZDH0401DW-7"))
    )
    (comp (ref "U3")
      (value "TCKE812NL,RF")
      (footprint "WSON10B_TOS")
      (description "5.1V Voltage Clmp Latch Type")
      (fields (field (name "MANUFACTURER") "Toshiba") (field (name "MANUFACTURER PART NUMBER") "TCKE812NLRF"))
      (libsource (lib "Virtex") (part "TCKE812NL,RF"))
    )
    (comp (ref "U4")
      (value "LM2738XMY/NOPB")
      (footprint "DGN0008A_N")
      (description "550kHz/1.6MHz 1.5A Step-Down DC-DC Switching Regulator, 8-pin eMSOP, Pb-Free")
      (fields (field (name "MANUFACTURER") "Texas Instruments"))
      (libsource (lib "Altium Content Vault") (part "PM-SWREG-LM2738-9"))
    )
  )
  (nets
    (net (code "1") (name "+1") (class "Default")
      (node (ref "C2") (pin "1") (pinfunction "1_1") (pintype "passive"))
      (node (ref "C3") (pin "1") (pinfunction "1_1") (pintype "passive"))
      (node (ref "C4") (pin "1") (pinfunction "1_1") (pintype "passive"))
      (node (ref "J2") (pin "11") (pintype "passive"))
      (node (ref "L1") (pin "2") (pinfunction "2_2") (pintype "passive"))
      (node (ref "U1") (pin "28") (pinfunction "OUTS1_28") (pintype "power_in"))
    )
    (net (code "2") (name "+1.8") (class "Default")
      (node (ref "C6") (pin "1") (pinfunction "1_1") (pintype "passive"))
      (node (ref "J2") (pin "5") (pintype "passive"))
      (node (ref "J2") (pin "6") (pintype "passive"))
      (node (ref "L2") (pin "2") (pinfunction "2_2") (pintype "passive"))
      (node (ref "U1") (pin "8") (pinfunction "OUTS2_8") (pintype "power_in"))
    )
    (net (code "3") (name "+2.5") (class "Default")
      (node (ref "C8") (pin "1") (pinfunction "1_1") (pintype "passive"))
      (node (ref "C9") (pin "2") (pinfunction "2_2") (pintype "passive"))
      (node (ref "J2") (pin "9") (pintype "passive"))
      (node (ref "L3") (pin "2") (pinfunction "2_2") (pintype "passive"))
      (node (ref "R12") (pin "2") (pinfunction "2_2") (pintype "passive"))
    )
    (net (code "4") (name "+3.3") (class "Default")
      (node (ref "C11") (pin "1") (pinfunction "1_1") (pintype "passive"))
      (node (ref "J2") (pin "1") (pintype "passive"))
      (node (ref "J2") (pin "2") (pintype "passive"))
      (node (ref "L4") (pin "2") (pinfunction "2_2") (pintype "passive"))
      (node (ref "R21") (pin "2") (pinfunction "2_2") (pintype "passive"))
      (node (ref "TP3") (pin "1") (pintype "passive"))
      (node (ref "U1") (pin "22") (pinfunction "OUTS4_22") (pintype "power_in"))
    )
    (net (code "5") (name "+5") (class "Default")
      (node (ref "C1") (pin "1") (pinfunction "1_1") (pintype "passive"))
      (node (ref "C10") (pin "1") (pinfunction "1_1") (pintype "passive"))
      (node (ref "C12") (pin "1") (pinfunction "1_1") (pintype "passive"))
      (node (ref "C22") (pin "1") (pinfunction "1_1") (pintype "passive"))
      (node (ref "C23") (pin "1") (pinfunction "1_1") (pintype "passive"))
      (node (ref "C24") (pin "1") (pinfunction "1_1") (pintype "passive"))
      (node (ref "C5") (pin "1") (pinfunction "1_1") (pintype "passive"))
      (node (ref "C7") (pin "1") (pinfunction "1_1") (pintype "passive"))
      (node (ref "D6") (pin "2") (pinfunction "A_2") (pintype "passive"))
      (node (ref "D7") (pin "2") (pinfunction "2_2") (pintype "passive"))
      (node (ref "J2") (pin "13") (pintype "passive"))
      (node (ref "J2") (pin "14") (pintype "passive"))
      (node (ref "L5") (pin "2") (pinfunction "2_2") (pintype "passive"))
      (node (ref "Q1") (pin "1") (pintype "power_in"))
      (node (ref "Q1") (pin "2") (pintype "power_in"))
      (node (ref "Q1") (pin "5") (pintype "power_in"))
      (node (ref "Q1") (pin "6") (pintype "power_in"))
      (node (ref "R10") (pin "1") (pinfunction "1_1") (pintype "passive"))
      (node (ref "R13") (pin "1") (pinfunction "1_1") (pintype "passive"))
      (node (ref "R22") (pin "2") (pinfunction "2_2") (pintype "passive"))
      (node (ref "R34") (pin "2") (pinfunction "2_2") (pintype "passive"))
      (node (ref "R8") (pin "1") (pinfunction "1_1") (pintype "passive"))
      (node (ref "R9") (pin "1") (pinfunction "1_1") (pintype "passive"))
      (node (ref "TP4") (pin "1") (pintype "passive"))
      (node (ref "U1") (pin "15") (pinfunction "PV3_15") (pintype "input"))
      (node (ref "U1") (pin "2") (pinfunction "PV1_2") (pintype "input"))
      (node (ref "U1") (pin "20") (pinfunction "PV4_20") (pintype "input"))
      (node (ref "U1") (pin "26") (pinfunction "VA_26") (pintype "power_in"))
      (node (ref "U1") (pin "7") (pinfunction "PV2_7") (pintype "input"))
      (node (ref "U2") (pin "4") (pinfunction "SOURCE_4") (pintype "passive"))
    )
    (net (code "6") (name "+5_USB") (class "Default")
      (node (ref "C14") (pin "1") (pinfunction "1_1") (pintype "passive"))
      (node (ref "FB1") (pin "2") (pinfunction "2_2") (pintype "passive"))
      (node (ref "Q1") (pin "4") (pintype "power_in"))
      (node (ref "R5") (pin "2") (pinfunction "2_2") (pintype "passive"))
      (node (ref "TP2") (pin "1") (pintype "passive"))
      (node (ref "U2") (pin "6") (pinfunction "DRAIN_6") (pintype "passive"))
    )
    (net (code "7") (name "+5_USB_UNF") (class "Default")
      (node (ref "C13") (pin "2") (pinfunction "2_2") (pintype "passive"))
      (node (ref "F1") (pin "2") (pinfunction "2_2") (pintype "passive"))
      (node (ref "FB1") (pin "1") (pinfunction "1_1") (pintype "passive"))
    )
    (net (code "8") (name "+5_USB_UNP") (class "Default")
      (node (ref "D3") (pin "4") (pinfunction "VCC_4") (pintype "power_in"))
      (node (ref "F1") (pin "1") (pinfunction "1_1") (pintype "passive"))
      (node (ref "J1") (pin "A4-B9") (pinfunction "VBUS_A4-B9") (pintype "power_in"))
      (node (ref "J1") (pin "B4-A9") (pinfunction "VBUS_B4-A9") (pintype "bidirectional"))
    )
    (net (code "9") (name "+12_CAB") (class "Default")
      (node (ref "C15") (pin "2") (pinfunction "2_2") (pintype "passive"))
      (node (ref "C19") (pin "1") (pinfunction "1_1") (pintype "passive"))
      (node (ref "C20") (pin "1") (pinfunction "1_1") (pintype "passive"))
      (node (ref "C21") (pin "1") (pinfunction "1_1") (pintype "passive"))
      (node (ref "J2") (pin "23") (pintype "passive"))
      (node (ref "J2") (pin "24") (pintype "passive"))
      (node (ref "J2") (pin "25") (pintype "passive"))
      (node (ref "Q2") (pin "2") (pinfunction "S_2") (pintype "passive"))
      (node (ref "U4") (pin "2") (pinfunction "IN_2") (pintype "power_in"))
      (node (ref "U4") (pin "3") (pinfunction "VCC_3") (pintype "power_in"))
      (node (ref "U4") (pin "4") (pinfunction "EN_4") (pintype "input"))
    )
    (net (code "10") (name "+12_CAB_UNP1") (class "Default")
      (node (ref "Q2") (pin "3") (pinfunction "D_3") (pintype "passive"))
      (node (ref "U3") (pin "6") (pinfunction "VOUT_6") (pintype "power_in"))
      (node (ref "U3") (pin "7") (pinfunction "VOUT_7") (pintype "power_in"))
      (node (ref "U3") (pin "8") (pinfunction "VOUT_8") (pintype "power_in"))
    )
    (net (code "11") (name "+12_CAB_UNP2") (class "Default")
      (node (ref "C16") (pin "2") (pinfunction "2_2") (pintype "passive"))
      (node (ref "Q3") (pin "4") (pintype "power_in"))
      (node (ref "R17") (pin "2") (pinfunction "2_2") (pintype "passive"))
      (node (ref "U3") (pin "3") (pinfunction "VIN_3") (pintype "power_in"))
      (node (ref "U3") (pin "4") (pinfunction "VIN_4") (pintype "power_in"))
      (node (ref "U3") (pin "5") (pinfunction "VIN_5") (pintype "power_in"))
    )
    (net (code "12") (name "+12_CAB_UNP3") (class "Default")
      (node (ref "D12") (pin "2") (pinfunction "2_2") (pintype "passive"))
      (node (ref "J3") (pin "2") (pinfunction "+12V_(RED)_2") (pintype "power_in"))
      (node (ref "Q3") (pin "1") (pintype "power_in"))
      (node (ref "Q3") (pin "2") (pintype "power_in"))
      (node (ref "Q3") (pin "5") (pintype "power_in"))
      (node (ref "Q3") (pin "6") (pintype "power_in"))
    )
    (net (code "13") (name "/1.8V_EN") (class "Default")
      (node (ref "R35") (pin "1") (pinfunction "1_1") (pintype "passive"))
      (node (ref "U1") (pin "9") (pinfunction "EN2_9") (pintype "input"))
    )
    (net (code "14") (name "/1.8V_LX") (class "Default")
      (node (ref "L2") (pin "1") (pinfunction "1_1") (pintype "passive"))
      (node (ref "U1") (pin "6") (pinfunction "LX2_6") (pintype "power_in"))
    )
    (net (code "15") (name "/1.8V_PG") (class "Default")
      (node (ref "J2") (pin "16") (pintype "passive"))
      (node (ref "R36") (pin "2") (pinfunction "2_2") (pintype "passive"))
      (node (ref "R9") (pin "2") (pinfunction "2_2") (pintype "passive"))
      (node (ref "U1") (pin "10") (pinfunction "PG2_10") (pintype "output"))
    )
    (net (code "16") (name "/1V_EN") (class "Default")
      (node (ref "R34") (pin "1") (pinfunction "1_1") (pintype "passive"))
      (node (ref "U1") (pin "1") (pinfunction "EN1_1") (pintype "input"))
    )
    (net (code "17") (name "/1V_LX") (class "Default")
      (node (ref "L1") (pin "1") (pinfunction "1_1") (pintype "passive"))
      (node (ref "U1") (pin "3") (pinfunction "LX1_3") (pintype "power_in"))
    )
    (net (code "18") (name "/1V_PG") (class "Default")
      (node (ref "R35") (pin "2") (pinfunction "2_2") (pintype "passive"))
      (node (ref "R8") (pin "2") (pinfunction "2_2") (pintype "passive"))
      (node (ref "U1") (pin "27") (pinfunction "PG1_27") (pintype "output"))
    )
    (net (code "19") (name "/2.5V_EN") (class "Default")
      (node (ref "R36") (pin "1") (pinfunction "1_1") (pintype "passive"))
      (node (ref "U1") (pin "13") (pinfunction "EN3_13") (pintype "input"))
    )
    (net (code "20") (name "/2.5V_LX") (class "Default")
      (node (ref "L3") (pin "1") (pinfunction "1_1") (pintype "passive"))
      (node (ref "U1") (pin "16") (pinfunction "LX3_16") (pintype "power_in"))
    )
    (net (code "21") (name "/2.5V_OUTS") (class "Default")
      (node (ref "C9") (pin "1") (pinfunction "1_1") (pintype "passive"))
      (node (ref "R12") (pin "1") (pinfunction "1_1") (pintype "passive"))
      (node (ref "R14") (pin "2") (pinfunction "2_2") (pintype "passive"))
      (node (ref "U1") (pin "14") (pinfunction "OUTS3_14") (pintype "power_in"))
    )
    (net (code "22") (name "/2.5V_PG") (class "Default")
      (node (ref "R10") (pin "2") (pinfunction "2_2") (pintype "passive"))
      (node (ref "R37") (pin "2") (pinfunction "2_2") (pintype "passive"))
      (node (ref "U1") (pin "12") (pinfunction "PG3_12") (pintype "output"))
    )
    (net (code "23") (name "/3.3V_EN") (class "Default")
      (node (ref "R37") (pin "1") (pinfunction "1_1") (pintype "passive"))
      (node (ref "U1") (pin "21") (pinfunction "EN4_21") (pintype "input"))
    )
    (net (code "24") (name "/3.3V_LX") (class "Default")
      (node (ref "L4") (pin "1") (pinfunction "1_1") (pintype "passive"))
      (node (ref "U1") (pin "19") (pinfunction "LX4_19") (pintype "power_in"))
    )
    (net (code "25") (name "/3.3V_PG") (class "Default")
      (node (ref "R13") (pin "2") (pinfunction "2_2") (pintype "passive"))
      (node (ref "TP1") (pin "1") (pintype "passive"))
      (node (ref "U1") (pin "23") (pinfunction "PG4_23") (pintype "output"))
    )
    (net (code "26") (name "/5V_BST") (class "Default")
      (node (ref "C18") (pin "1") (pinfunction "1_1") (pintype "passive"))
      (node (ref "D7") (pin "1") (pinfunction "1_1") (pintype "passive"))
      (node (ref "U4") (pin "1") (pinfunction "BST_1") (pintype "passive"))
    )
    (net (code "27") (name "/5V_FB") (class "Default")
      (node (ref "R22") (pin "1") (pinfunction "1_1") (pintype "passive"))
      (node (ref "R23") (pin "2") (pinfunction "2_2") (pintype "passive"))
      (node (ref "U4") (pin "6") (pinfunction "FB_6") (pintype "input"))
    )
    (net (code "28") (name "/5V_SW") (class "Default")
      (node (ref "C18") (pin "2") (pinfunction "2_2") (pintype "passive"))
      (node (ref "D13") (pin "1") (pinfunction "1_1") (pintype "passive"))
      (node (ref "L5") (pin "1") (pinfunction "1_1") (pintype "passive"))
      (node (ref "U4") (pin "8") (pinfunction "SW_8") (pintype "power_in"))
    )
    (net (code "29") (name "/12V_REV_SW") (class "Default")
      (node (ref "Q2") (pin "1") (pinfunction "G_1") (pintype "passive"))
      (node (ref "Q4") (pin "1") (pinfunction "G_1") (pintype "passive"))
      (node (ref "U3") (pin "9") (pinfunction "EFET_9") (pintype "output"))
    )
    (net (code "30") (name "/12V_RPP_SW") (class "Default")
      (node (ref "Q3") (pin "3") (pintype "input"))
      (node (ref "R20") (pin "2") (pinfunction "2_2") (pintype "passive"))
    )
    (net (code "31") (name "/12V_UVLO") (class "Default")
      (node (ref "R17") (pin "1") (pinfunction "1_1") (pintype "passive"))
      (node (ref "R18") (pin "2") (pinfunction "2_2") (pintype "passive"))
      (node (ref "U3") (pin "2") (pinfunction "EN/UVLO_2") (pintype "input"))
    )
    (net (code "32") (name "/PWR_12V_OFF") (class "Default")
      (node (ref "J2") (pin "19") (pintype "passive"))
      (node (ref "Q4") (pin "3") (pinfunction "D_3") (pintype "passive"))
      (node (ref "R21") (pin "1") (pinfunction "1_1") (pintype "passive"))
    )
    (net (code "33") (name "/RIO_CS") (class "Default")
      (node (ref "D8") (pin "1") (pinfunction "K_1") (pintype "passive"))
      (node (ref "J2") (pin "26") (pintype "passive"))
      (node (ref "R11") (pin "2") (pinfunction "2_2") (pintype "passive"))
    )
    (net (code "34") (name "/RIO_CS_UNP") (class "Default")
      (node (ref "D1") (pin "1") (pinfunction "1_1") (pintype "passive"))
      (node (ref "J3") (pin "6") (pinfunction "CS_(WHITE)_6") (pintype "output"))
      (node (ref "R11") (pin "1") (pinfunction "1_1") (pintype "passive"))
    )
    (net (code "35") (name "/RIO_MISO") (class "Default")
      (node (ref "D9") (pin "1") (pinfunction "K_1") (pintype "passive"))
      (node (ref "J2") (pin "27") (pintype "passive"))
      (node (ref "R7") (pin "2") (pinfunction "2_2") (pintype "passive"))
    )
    (net (code "36") (name "/RIO_MISO_UNP") (class "Default")
      (node (ref "D2") (pin "1") (pinfunction "1_1") (pintype "passive"))
      (node (ref "J3") (pin "5") (pinfunction "MISO_(GREEN)_5") (pintype "input"))
      (node (ref "R7") (pin "1") (pinfunction "1_1") (pintype "passive"))
    )
    (net (code "37") (name "/RIO_MOSI") (class "Default")
      (node (ref "D10") (pin "1") (pinfunction "K_1") (pintype "passive"))
      (node (ref "J2") (pin "28") (pintype "passive"))
      (node (ref "R3") (pin "2") (pinfunction "2_2") (pintype "passive"))
    )
    (net (code "38") (name "/RIO_MOSI_UNP") (class "Default")
      (node (ref "D4") (pin "1") (pinfunction "1_1") (pintype "passive"))
      (node (ref "J3") (pin "4") (pinfunction "MOSI_(BLUE)_4") (pintype "output"))
      (node (ref "R3") (pin "1") (pinfunction "1_1") (pintype "passive"))
    )
    (net (code "39") (name "/RIO_SCLK") (class "Default")
      (node (ref "D11") (pin "1") (pinfunction "K_1") (pintype "passive"))
      (node (ref "J2") (pin "29") (pintype "passive"))
      (node (ref "R1") (pin "2") (pinfunction "2_2") (pintype "passive"))
    )
    (net (code "40") (name "/RIO_SCLK_UNP") (class "Default")
      (node (ref "D5") (pin "1") (pinfunction "1_1") (pintype "passive"))
      (node (ref "J3") (pin "3") (pinfunction "SCLK_(YELLOW)_3") (pintype "output"))
      (node (ref "R1") (pin "1") (pinfunction "1_1") (pintype "passive"))
    )
    (net (code "41") (name "/USB_CC1") (class "Default")
      (node (ref "J1") (pin "A5") (pinfunction "CC1_A5") (pintype "power_in"))
      (node (ref "R2") (pin "1") (pinfunction "1_1") (pintype "passive"))
    )
    (net (code "42") (name "/USB_CC2") (class "Default")
      (node (ref "J1") (pin "B5") (pinfunction "CC2_B5") (pintype "bidirectional"))
      (node (ref "R4") (pin "1") (pinfunction "1_1") (pintype "passive"))
    )
    (net (code "43") (name "/USB_CLKOUT") (class "Default") (node (ref "J2") (pin "36") (pintype "passive")))
    (net (code "44") (name "/USB_D0") (class "Default") (node (ref "J2") (pin "50") (pintype "passive")))
    (net (code "45") (name "/USB_D1") (class "Default") (node (ref "J2") (pin "49") (pintype "passive")))
    (net (code "46") (name "/USB_D2") (class "Default") (node (ref "J2") (pin "48") (pintype "passive")))
    (net (code "47") (name "/USB_D3") (class "Default") (node (ref "J2") (pin "47") (pintype "passive")))
    (net (code "48") (name "/USB_D4") (class "Default") (node (ref "J2") (pin "46") (pintype "passive")))
    (net (code "49") (name "/USB_D5") (class "Default") (node (ref "J2") (pin "45") (pintype "passive")))
    (net (code "50") (name "/USB_D6") (class "Default") (node (ref "J2") (pin "44") (pintype "passive")))
    (net (code "51") (name "/USB_D7") (class "Default") (node (ref "J2") (pin "43") (pintype "passive")))
    (net (code "52") (name "/USB_N") (class "Default")
      (node (ref "D3") (pin "2") (pinfunction "I/O1_2") (pintype "bidirectional"))
      (node (ref "J1") (pin "A7") (pinfunction "Dn1_A7") (pintype "bidirectional"))
      (node (ref "J1") (pin "B7") (pinfunction "Dn2_B7") (pintype "bidirectional"))
    )
    (net (code "53") (name "/USB_OE") (class "Default") (node (ref "J2") (pin "35") (pintype "passive")))
    (net (code "54") (name "/USB_ON") (class "Default")
      (node (ref "R5") (pin "1") (pinfunction "1_1") (pintype "passive"))
      (node (ref "R6") (pin "2") (pinfunction "2_2") (pintype "passive"))
    )
    (net (code "55") (name "/USB_P") (class "Default")
      (node (ref "D3") (pin "3") (pinfunction "I/O2_3") (pintype "bidirectional"))
      (node (ref "J1") (pin "A6") (pinfunction "Dp1_A6") (pintype "bidirectional"))
      (node (ref "J1") (pin "B6") (pinfunction "Dp2_B6") (pintype "bidirectional"))
    )
    (net (code "56") (name "/USB_PWREN") (class "Default") (node (ref "J2") (pin "17") (pintype "passive")))
    (net (code "57") (name "/USB_RD") (class "Default") (node (ref "J2") (pin "39") (pintype "passive")))
    (net (code "58") (name "/USB_REV_SW") (class "Default")
      (node (ref "Q1") (pin "3") (pintype "input"))
      (node (ref "R16") (pin "1") (pinfunction "1_1") (pintype "passive"))
      (node (ref "U2") (pin "3") (pinfunction "BIAS_3") (pintype "passive"))
    )
    (net (code "59") (name "/USB_RXF") (class "Default") (node (ref "J2") (pin "41") (pintype "passive")))
    (net (code "60") (name "/USB_SIWU") (class "Default") (node (ref "J2") (pin "37") (pintype "passive")))
    (net (code "61") (name "/USB_SUS") (class "Default") (node (ref "J2") (pin "18") (pintype "passive")))
    (net (code "62") (name "/USB_TCK") (class "Default") (node (ref "J2") (pin "33") (pintype "passive")))
    (net (code "63") (name "/USB_TDI") (class "Default") (node (ref "J2") (pin "32") (pintype "passive")))
    (net (code "64") (name "/USB_TDO") (class "Default") (node (ref "J2") (pin "31") (pintype "passive")))
    (net (code "65") (name "/USB_TMS") (class "Default") (node (ref "J2") (pin "30") (pintype "passive")))
    (net (code "66") (name "/USB_TXE") (class "Default") (node (ref "J2") (pin "40") (pintype "passive")))
    (net (code "67") (name "/USB_WR") (class "Default") (node (ref "J2") (pin "38") (pintype "passive")))
    (net (code "68") (name "ENC") (class "Default")
      (node (ref "J1") (pin "1") (pinfunction "MNT_1_1") (pintype "power_in"))
      (node (ref "J1") (pin "2") (pinfunction "MNT_2_2") (pintype "power_in"))
      (node (ref "J1") (pin "3") (pinfunction "MNT_3_3") (pintype "power_in"))
      (node (ref "J1") (pin "4") (pinfunction "MNT_4_4") (pintype "power_in"))
      (node (ref "M1") (pin "1") (pintype "passive"))
      (node (ref "M2") (pin "1") (pintype "passive"))
    )
    (net (code "69") (name "GND") (class "Default")
      (node (ref "C1") (pin "2") (pinfunction "2_2") (pintype "passive"))
      (node (ref "C10") (pin "2") (pinfunction "2_2") (pintype "passive"))
      (node (ref "C11") (pin "2") (pinfunction "2_2") (pintype "passive"))
      (node (ref "C12") (pin "2") (pinfunction "2_2") (pintype "passive"))
      (node (ref "C13") (pin "1") (pinfunction "1_1") (pintype "passive"))
      (node (ref "C14") (pin "2") (pinfunction "2_2") (pintype "passive"))
      (node (ref "C15") (pin "1") (pinfunction "1_1") (pintype "passive"))
      (node (ref "C16") (pin "1") (pinfunction "1_1") (pintype "passive"))
      (node (ref "C17") (pin "1") (pinfunction "1_1") (pintype "passive"))
      (node (ref "C19") (pin "2") (pinfunction "2_2") (pintype "passive"))
      (node (ref "C2") (pin "2") (pinfunction "2_2") (pintype "passive"))
      (node (ref "C20") (pin "2") (pinfunction "2_2") (pintype "passive"))
      (node (ref "C21") (pin "2") (pinfunction "2_2") (pintype "passive"))
      (node (ref "C22") (pin "2") (pinfunction "2_2") (pintype "passive"))
      (node (ref "C23") (pin "2") (pinfunction "2_2") (pintype "passive"))
      (node (ref "C24") (pin "2") (pinfunction "2_2") (pintype "passive"))
      (node (ref "C3") (pin "2") (pinfunction "2_2") (pintype "passive"))
      (node (ref "C4") (pin "2") (pinfunction "2_2") (pintype "passive"))
      (node (ref "C5") (pin "2") (pinfunction "2_2") (pintype "passive"))
      (node (ref "C6") (pin "2") (pinfunction "2_2") (pintype "passive"))
      (node (ref "C7") (pin "2") (pinfunction "2_2") (pintype "passive"))
      (node (ref "C8") (pin "2") (pinfunction "2_2") (pintype "passive"))
      (node (ref "D1") (pin "2") (pinfunction "2_2") (pintype "passive"))
      (node (ref "D10") (pin "2") (pinfunction "A_2") (pintype "passive"))
      (node (ref "D11") (pin "2") (pinfunction "A_2") (pintype "passive"))
      (node (ref "D12") (pin "1") (pinfunction "1_1") (pintype "passive"))
      (node (ref "D13") (pin "2") (pinfunction "2_2") (pintype "passive"))
      (node (ref "D2") (pin "2") (pinfunction "2_2") (pintype "passive"))
      (node (ref "D3") (pin "1") (pinfunction "GND_1") (pintype "power_in"))
      (node (ref "D4") (pin "2") (pinfunction "2_2") (pintype "passive"))
      (node (ref "D5") (pin "2") (pinfunction "2_2") (pintype "passive"))
      (node (ref "D8") (pin "2") (pinfunction "A_2") (pintype "passive"))
      (node (ref "D9") (pin "2") (pinfunction "A_2") (pintype "passive"))
      (node (ref "J1") (pin "A1-B12") (pinfunction "GND_A1-B12") (pintype "power_in"))
      (node (ref "J1") (pin "B1-A12") (pinfunction "GND_B1-A12") (pintype "bidirectional"))
      (node (ref "J2") (pin "10") (pintype "passive"))
      (node (ref "J2") (pin "12") (pintype "passive"))
      (node (ref "J2") (pin "15") (pintype "passive"))
      (node (ref "J2") (pin "20") (pintype "passive"))
      (node (ref "J2") (pin "21") (pintype "passive"))
      (node (ref "J2") (pin "22") (pintype "passive"))
      (node (ref "J2") (pin "3") (pintype "passive"))
      (node (ref "J2") (pin "34") (pintype "passive"))
      (node (ref "J2") (pin "4") (pintype "passive"))
      (node (ref "J2") (pin "42") (pintype "passive"))
      (node (ref "J2") (pin "7") (pintype "passive"))
      (node (ref "J2") (pin "8") (pintype "passive"))
      (node (ref "J2") (pin "MNT") (pintype "passive"))
      (node (ref "J3") (pin "1") (pinfunction "GND_(BLACK)_1") (pintype "power_in"))
      (node (ref "Q4") (pin "2") (pinfunction "S_2") (pintype "passive"))
      (node (ref "R14") (pin "1") (pinfunction "1_1") (pintype "passive"))
      (node (ref "R15") (pin "2") (pinfunction "2_2") (pintype "passive"))
      (node (ref "R16") (pin "2") (pinfunction "2_2") (pintype "passive"))
      (node (ref "R18") (pin "1") (pinfunction "1_1") (pintype "passive"))
      (node (ref "R19") (pin "2") (pinfunction "2_2") (pintype "passive"))
      (node (ref "R2") (pin "2") (pinfunction "2_2") (pintype "passive"))
      (node (ref "R20") (pin "1") (pinfunction "1_1") (pintype "passive"))
      (node (ref "R23") (pin "1") (pinfunction "1_1") (pintype "passive"))
      (node (ref "R38") (pin "2") (pinfunction "2_2") (pintype "passive"))
      (node (ref "R4") (pin "2") (pinfunction "2_2") (pintype "passive"))
      (node (ref "R6") (pin "1") (pinfunction "1_1") (pintype "passive"))
      (node (ref "U1") (pin "11") (pinfunction "GND_11") (pintype "power_in"))
      (node (ref "U1") (pin "17") (pinfunction "PGND3_17") (pintype "power_in"))
      (node (ref "U1") (pin "18") (pinfunction "PGND4_18") (pintype "power_in"))
      (node (ref "U1") (pin "24") (pinfunction "GND_24") (pintype "power_in"))
      (node (ref "U1") (pin "25") (pinfunction "SYNC_25") (pintype "input"))
      (node (ref "U1") (pin "29") (pinfunction "EPAD_29") (pintype "passive"))
      (node (ref "U1") (pin "4") (pinfunction "PGND1_4") (pintype "power_in"))
      (node (ref "U1") (pin "5") (pinfunction "PGND2_5") (pintype "power_in"))
      (node (ref "U3") (pin "11") (pinfunction "EPAD_11") (pintype "power_in"))
      (node (ref "U4") (pin "5") (pinfunction "GND_5") (pintype "power_in"))
      (node (ref "U4") (pin "7") (pinfunction "GND_7") (pintype "power_in"))
      (node (ref "U4") (pin "9") (pinfunction "EP_9") (pintype "power_in"))
    )
    (net (code "70") (name "Net-(D6-C)") (class "Default")
      (node (ref "D6") (pin "1") (pinfunction "C_1") (pintype "passive"))
      (node (ref "R38") (pin "1") (pinfunction "1_1") (pintype "passive"))
    )
    (net (code "71") (name "Net-(U2-REF)") (class "Default")
      (node (ref "R15") (pin "1") (pinfunction "1_1") (pintype "passive"))
      (node (ref "U2") (pin "2") (pinfunction "REF_2") (pintype "passive"))
    )
    (net (code "72") (name "Net-(U3-ILIM)") (class "Default")
      (node (ref "R19") (pin "1") (pinfunction "1_1") (pintype "passive"))
      (node (ref "U3") (pin "10") (pinfunction "ILIM_10") (pintype "input"))
    )
    (net (code "73") (name "Net-(U3-dV{slash}dT)") (class "Default")
      (node (ref "C17") (pin "2") (pinfunction "2_2") (pintype "passive"))
      (node (ref "U3") (pin "1") (pinfunction "dV/dT_1") (pintype "input"))
    )
    (net (code "74") (name "unconnected-(J1-SBU1-PadA8)") (class "Default")
      (node (ref "J1") (pin "A8") (pinfunction "SBU1_A8") (pintype "bidirectional+no_connect"))
    )
    (net (code "75") (name "unconnected-(J1-SBU2-PadB8)") (class "Default")
      (node (ref "J1") (pin "B8") (pinfunction "SBU2_B8") (pintype "power_in+no_connect"))
    )
    (net (code "76") (name "unconnected-(U2-NC-Pad1)") (class "Default")
      (node (ref "U2") (pin "1") (pinfunction "NC_1") (pintype "passive+no_connect"))
    )
    (net (code "77") (name "unconnected-(U2-NC-Pad5)") (class "Default")
      (node (ref "U2") (pin "5") (pinfunction "NC_5") (pintype "passive+no_connect"))
    )
  )
)
